# DensityAltitude.net
KiCad netlist of a schematic drawn in EAGLE
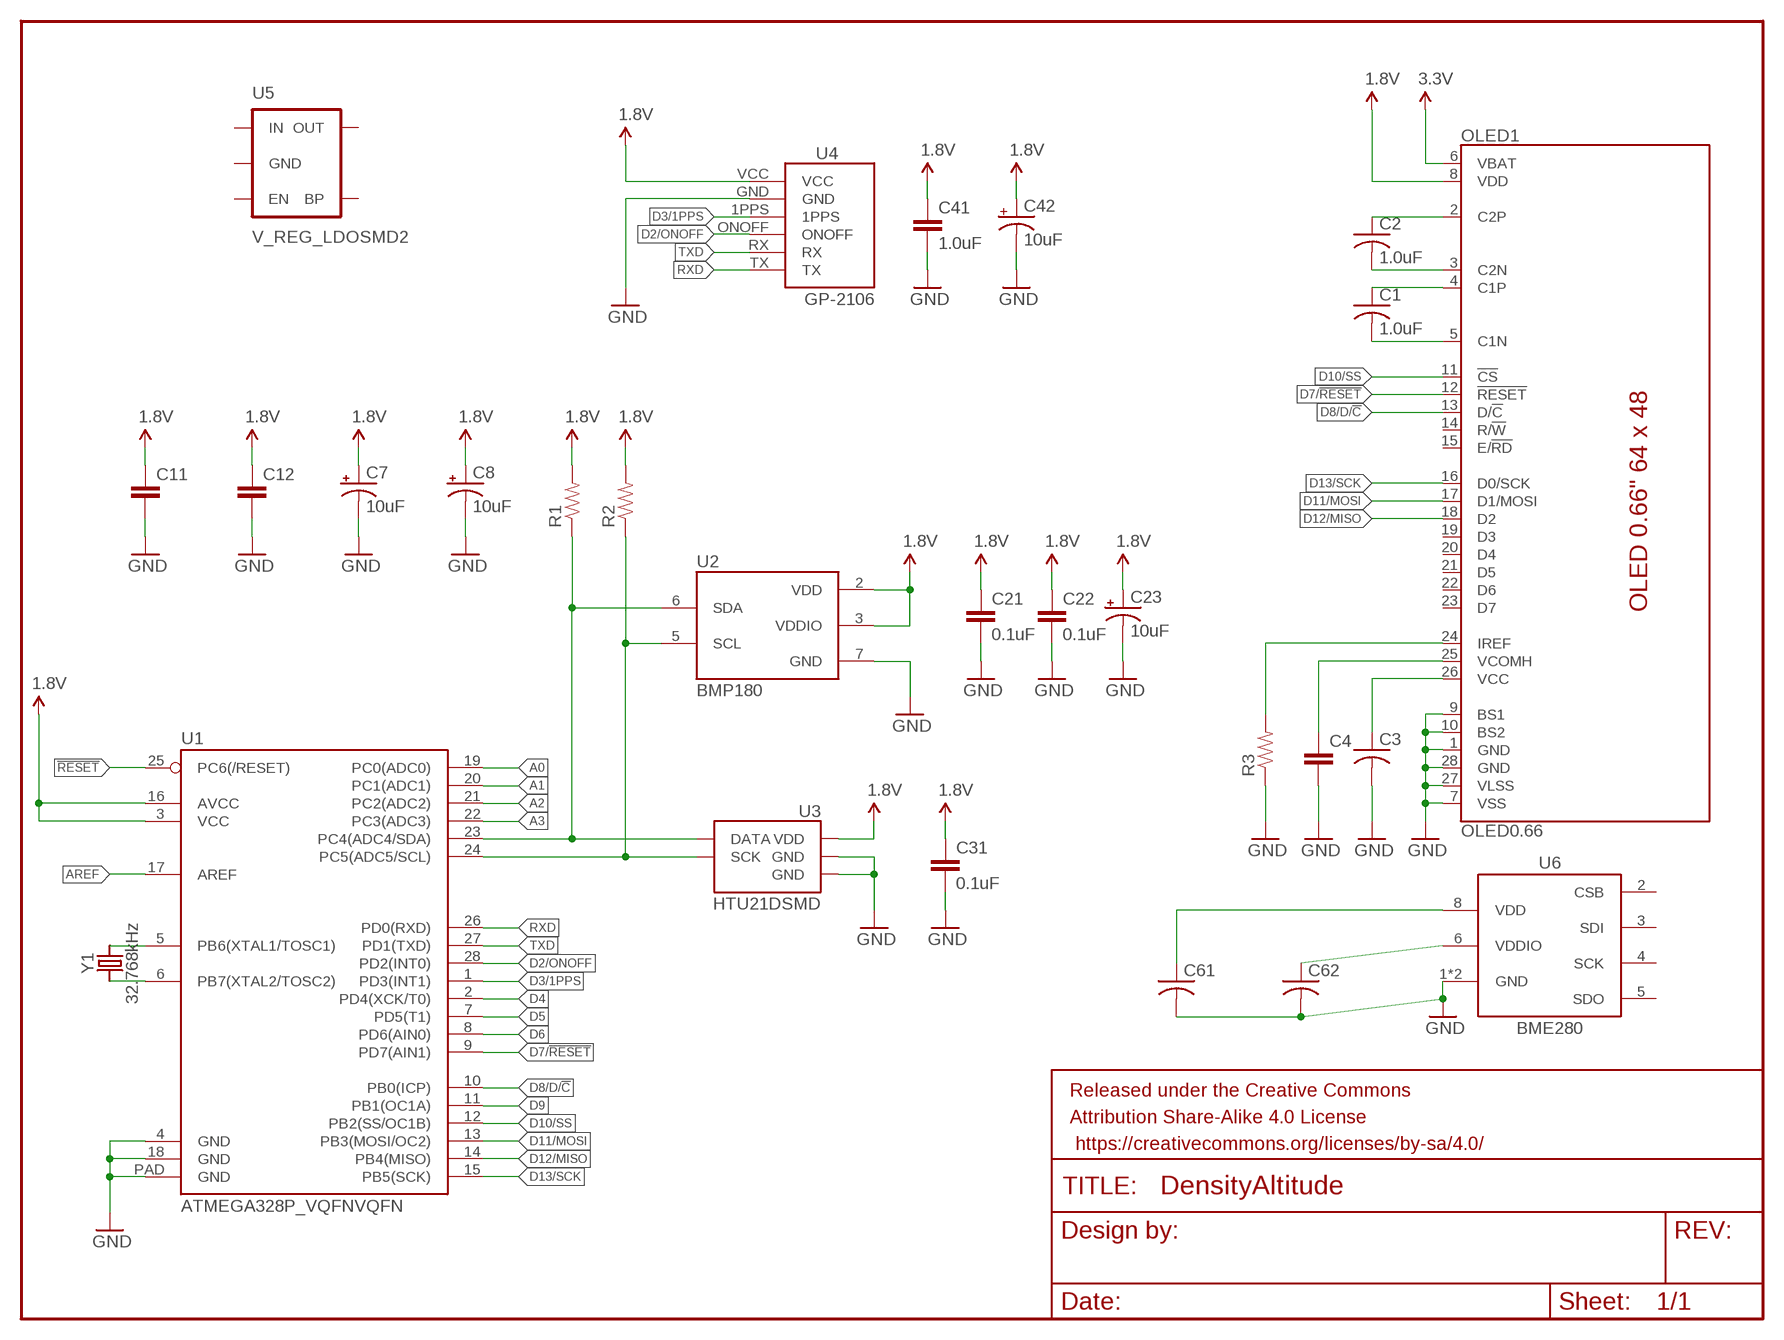
[diagram p0: schematic, sheet 1]

(export (version "E")
  (design (tool "Eeschema 10.0.6"))
  (components
    (comp (ref "C1")
      (value "1.0uF")
      (footprint "eagle-import:C0201")
      (libsource (lib "eagle-import") (part "C-USC0201"))
    )
    (comp (ref "C2")
      (value "1.0uF")
      (footprint "eagle-import:C0201")
      (libsource (lib "eagle-import") (part "C-USC0201"))
    )
    (comp (ref "C3")
      (value "C-USC0201")
      (footprint "eagle-import:C0201")
      (libsource (lib "eagle-import") (part "C-USC0201"))
    )
    (comp (ref "C4")
      (value "CAP0402-CAP")
      (footprint "eagle-import:0402-CAP")
      (libsource (lib "eagle-import") (part "CAP0402-CAP"))
    )
    (comp (ref "C7")
      (value "10uF")
      (footprint "eagle-import:EIA3216")
      (libsource (lib "eagle-import") (part "10UF-16V-10%(TANT)"))
    )
    (comp (ref "C8")
      (value "10uF")
      (footprint "eagle-import:EIA3216")
      (libsource (lib "eagle-import") (part "10UF-16V-10%(TANT)"))
    )
    (comp (ref "C11")
      (value "CAP0402-CAP")
      (footprint "eagle-import:0402-CAP")
      (libsource (lib "eagle-import") (part "CAP0402-CAP"))
    )
    (comp (ref "C12")
      (value "CAP0402-CAP")
      (footprint "eagle-import:0402-CAP")
      (libsource (lib "eagle-import") (part "CAP0402-CAP"))
    )
    (comp (ref "C21")
      (value "0.1uF")
      (footprint "eagle-import:0402-CAP")
      (libsource (lib "eagle-import") (part "0.1UF-16V(+-10%)(0402)"))
    )
    (comp (ref "C22")
      (value "0.1uF")
      (footprint "eagle-import:0402-CAP")
      (libsource (lib "eagle-import") (part "0.1UF-16V(+-10%)(0402)"))
    )
    (comp (ref "C23")
      (value "10uF")
      (footprint "eagle-import:EIA3216")
      (libsource (lib "eagle-import") (part "10UF-16V-10%(TANT)"))
    )
    (comp (ref "C31")
      (value "0.1uF")
      (footprint "eagle-import:0402-CAP")
      (libsource (lib "eagle-import") (part "0.1UF-16V(+-10%)(0402)"))
    )
    (comp (ref "C41")
      (value "1.0uF")
      (footprint "eagle-import:0402-CAP")
      (libsource (lib "eagle-import") (part "1.0UF-16V-10%(0402)"))
    )
    (comp (ref "C42")
      (value "10uF")
      (footprint "eagle-import:EIA3216")
      (libsource (lib "eagle-import") (part "10UF-16V-10%(TANT)"))
    )
    (comp (ref "C61")
      (value "C-USC0201")
      (footprint "eagle-import:C0201")
      (libsource (lib "eagle-import") (part "C-USC0201"))
    )
    (comp (ref "C62")
      (value "C-USC0201")
      (footprint "eagle-import:C0201")
      (libsource (lib "eagle-import") (part "C-USC0201"))
    )
    (comp (ref "FRAME1")
      (value "FRAME-LETTER")
      (footprint "eagle-import:CREATIVE_COMMONS")
      (fields (field (name "DESIGNER") "NAME"))
      (libsource (lib "eagle-import") (part "FRAME-LETTER"))
    )
    (comp (ref "OLED1")
      (value "OLED0.66")
      (footprint "eagle-import:OLED-0.66-64X48")
      (libsource (lib "eagle-import") (part "OLED0.66"))
    )
    (comp (ref "R1")
      (value "RESISTOR0402-RES")
      (footprint "eagle-import:0402-RES")
      (libsource (lib "eagle-import") (part "RESISTOR0402-RES"))
    )
    (comp (ref "R2")
      (value "RESISTOR0402-RES")
      (footprint "eagle-import:0402-RES")
      (libsource (lib "eagle-import") (part "RESISTOR0402-RES"))
    )
    (comp (ref "R3")
      (value "RESISTOR0402-RES")
      (footprint "eagle-import:0402-RES")
      (libsource (lib "eagle-import") (part "RESISTOR0402-RES"))
    )
    (comp (ref "U1")
      (value "ATMEGA328P_VQFNVQFN")
      (footprint "eagle-import:VQFN-28")
      (libsource (lib "eagle-import") (part "ATMEGA328P_VQFNVQFN"))
    )
    (comp (ref "U2")
      (value "BMP180")
      (footprint "eagle-import:BMP180")
      (libsource (lib "eagle-import") (part "BMP180"))
    )
    (comp (ref "U3")
      (value "HTU21DSMD")
      (footprint "eagle-import:HTU21D")
      (libsource (lib "eagle-import") (part "HTU21DSMD"))
    )
    (comp (ref "U4")
      (value "GP-2106")
      (footprint "eagle-import:GP-2106")
      (libsource (lib "eagle-import") (part "GP-2106"))
    )
    (comp (ref "U5")
      (value "V_REG_LDOSMD2")
      (footprint "eagle-import:SC70")
      (libsource (lib "eagle-import") (part "V_REG_LDOSMD2"))
    )
    (comp (ref "U6")
      (value "BME280")
      (footprint "eagle-import:BME280")
      (libsource (lib "eagle-import") (part "BME280"))
    )
    (comp (ref "Y1")
      (value "32.768kHz")
      (footprint "eagle-import:2-SMD")
      (libsource (lib "eagle-import") (part "FX12232.768KHZ"))
    )
  )
  (nets
    (net (code "1") (name "/D7{slash}~{RESET}") (class "Default")
      (node (ref "OLED1") (pin "12") (pinfunction "~{RESET}_12") (pintype "bidirectional"))
      (node (ref "U1") (pin "9") (pinfunction "PD7(AIN1)_9") (pintype "bidirectional"))
    )
    (net (code "2") (name "/D8{slash}D{slash}~{C}") (class "Default")
      (node (ref "OLED1") (pin "13") (pinfunction "D/~{C}_13") (pintype "bidirectional"))
      (node (ref "U1") (pin "10") (pinfunction "PB0(ICP)_10") (pintype "bidirectional"))
    )
    (net (code "3") (name "/~{RESET}") (class "Default")
      (node (ref "U1") (pin "25") (pinfunction "PC6(/RESET)_25") (pintype "bidirectional"))
    )
    (net (code "4") (name "1.8V") (class "Default")
      (node (ref "C11") (pin "1") (pinfunction "1_1") (pintype "passive"))
      (node (ref "C12") (pin "1") (pinfunction "1_1") (pintype "passive"))
      (node (ref "C21") (pin "1") (pinfunction "1_1") (pintype "passive"))
      (node (ref "C22") (pin "1") (pinfunction "1_1") (pintype "passive"))
      (node (ref "C23") (pin "A") (pinfunction "+_A") (pintype "passive"))
      (node (ref "C31") (pin "1") (pinfunction "1_1") (pintype "passive"))
      (node (ref "C41") (pin "1") (pinfunction "1_1") (pintype "passive"))
      (node (ref "C42") (pin "A") (pinfunction "+_A") (pintype "passive"))
      (node (ref "C7") (pin "A") (pinfunction "+_A") (pintype "passive"))
      (node (ref "C8") (pin "A") (pinfunction "+_A") (pintype "passive"))
      (node (ref "OLED1") (pin "8") (pinfunction "VDD_8") (pintype "bidirectional"))
      (node (ref "R1") (pin "2") (pinfunction "2_2") (pintype "passive"))
      (node (ref "R2") (pin "2") (pinfunction "2_2") (pintype "passive"))
      (node (ref "U1") (pin "16") (pinfunction "AVCC_16") (pintype "bidirectional"))
      (node (ref "U1") (pin "3") (pinfunction "VCC_3") (pintype "bidirectional"))
      (node (ref "U2") (pin "2") (pinfunction "VDD_2") (pintype "power_in"))
      (node (ref "U2") (pin "3") (pinfunction "VDDIO_3") (pintype "power_in"))
      (node (ref "U3") (pin "VDD") (pinfunction "VDD_VDD") (pintype "power_in"))
      (node (ref "U4") (pin "VCC") (pinfunction "VCC_VCC") (pintype "bidirectional"))
    )
    (net (code "5") (name "3.3V") (class "Default")
      (node (ref "OLED1") (pin "6") (pinfunction "VBAT_6") (pintype "bidirectional"))
    )
    (net (code "6") (name "A0") (class "Default")
      (node (ref "U1") (pin "19") (pinfunction "PC0(ADC0)_19") (pintype "bidirectional"))
    )
    (net (code "7") (name "A1") (class "Default")
      (node (ref "U1") (pin "20") (pinfunction "PC1(ADC1)_20") (pintype "bidirectional"))
    )
    (net (code "8") (name "A2") (class "Default")
      (node (ref "U1") (pin "21") (pinfunction "PC2(ADC2)_21") (pintype "bidirectional"))
    )
    (net (code "9") (name "A3") (class "Default")
      (node (ref "U1") (pin "22") (pinfunction "PC3(ADC3)_22") (pintype "bidirectional"))
    )
    (net (code "10") (name "AREF") (class "Default")
      (node (ref "U1") (pin "17") (pinfunction "AREF_17") (pintype "bidirectional"))
    )
    (net (code "11") (name "D2{slash}ONOFF") (class "Default")
      (node (ref "U1") (pin "28") (pinfunction "PD2(INT0)_28") (pintype "bidirectional"))
      (node (ref "U4") (pin "ONOFF") (pinfunction "ONOFF_ONOFF") (pintype "bidirectional"))
    )
    (net (code "12") (name "D3{slash}1PPS") (class "Default")
      (node (ref "U1") (pin "1") (pinfunction "PD3(INT1)_1") (pintype "bidirectional"))
      (node (ref "U4") (pin "1PPS") (pinfunction "1PPS_1PPS") (pintype "bidirectional"))
    )
    (net (code "13") (name "D4") (class "Default")
      (node (ref "U1") (pin "2") (pinfunction "PD4(XCK/T0)_2") (pintype "bidirectional"))
    )
    (net (code "14") (name "D5") (class "Default")
      (node (ref "U1") (pin "7") (pinfunction "PD5(T1)_7") (pintype "bidirectional"))
    )
    (net (code "15") (name "D6") (class "Default")
      (node (ref "U1") (pin "8") (pinfunction "PD6(AIN0)_8") (pintype "bidirectional"))
    )
    (net (code "16") (name "D9") (class "Default")
      (node (ref "U1") (pin "11") (pinfunction "PB1(OC1A)_11") (pintype "bidirectional"))
    )
    (net (code "17") (name "D10{slash}SS") (class "Default")
      (node (ref "OLED1") (pin "11") (pinfunction "~{CS}_11") (pintype "bidirectional"))
      (node (ref "U1") (pin "12") (pinfunction "PB2(SS/OC1B)_12") (pintype "bidirectional"))
    )
    (net (code "18") (name "D11{slash}MOSI") (class "Default")
      (node (ref "OLED1") (pin "17") (pinfunction "D1/MOSI_17") (pintype "bidirectional"))
      (node (ref "U1") (pin "13") (pinfunction "PB3(MOSI/OC2)_13") (pintype "bidirectional"))
    )
    (net (code "19") (name "D12{slash}MISO") (class "Default")
      (node (ref "OLED1") (pin "18") (pinfunction "D2_18") (pintype "bidirectional"))
      (node (ref "U1") (pin "14") (pinfunction "PB4(MISO)_14") (pintype "bidirectional"))
    )
    (net (code "20") (name "D13{slash}SCK") (class "Default")
      (node (ref "OLED1") (pin "16") (pinfunction "D0/SCK_16") (pintype "bidirectional"))
      (node (ref "U1") (pin "15") (pinfunction "PB5(SCK)_15") (pintype "bidirectional"))
    )
    (net (code "21") (name "GND") (class "Default")
      (node (ref "C11") (pin "2") (pinfunction "2_2") (pintype "passive"))
      (node (ref "C12") (pin "2") (pinfunction "2_2") (pintype "passive"))
      (node (ref "C21") (pin "2") (pinfunction "2_2") (pintype "passive"))
      (node (ref "C22") (pin "2") (pinfunction "2_2") (pintype "passive"))
      (node (ref "C23") (pin "C") (pinfunction "-_C") (pintype "passive"))
      (node (ref "C3") (pin "2") (pinfunction "2_2") (pintype "passive"))
      (node (ref "C31") (pin "2") (pinfunction "2_2") (pintype "passive"))
      (node (ref "C4") (pin "2") (pinfunction "2_2") (pintype "passive"))
      (node (ref "C41") (pin "2") (pinfunction "2_2") (pintype "passive"))
      (node (ref "C42") (pin "C") (pinfunction "-_C") (pintype "passive"))
      (node (ref "C61") (pin "2") (pinfunction "2_2") (pintype "passive"))
      (node (ref "C62") (pin "2") (pinfunction "2_2") (pintype "passive"))
      (node (ref "C7") (pin "C") (pinfunction "-_C") (pintype "passive"))
      (node (ref "C8") (pin "C") (pinfunction "-_C") (pintype "passive"))
      (node (ref "OLED1") (pin "1") (pinfunction "GND_1") (pintype "bidirectional"))
      (node (ref "OLED1") (pin "10") (pinfunction "BS2_10") (pintype "bidirectional"))
      (node (ref "OLED1") (pin "27") (pinfunction "VLSS_27") (pintype "bidirectional"))
      (node (ref "OLED1") (pin "28") (pinfunction "GND_28") (pintype "bidirectional"))
      (node (ref "OLED1") (pin "7") (pinfunction "VSS_7") (pintype "bidirectional"))
      (node (ref "OLED1") (pin "9") (pinfunction "BS1_9") (pintype "bidirectional"))
      (node (ref "R3") (pin "1") (pinfunction "1_1") (pintype "passive"))
      (node (ref "U1") (pin "18") (pinfunction "GND_18") (pintype "bidirectional"))
      (node (ref "U1") (pin "4") (pinfunction "GND_4") (pintype "bidirectional"))
      (node (ref "U1") (pin "PAD") (pinfunction "GND_PAD") (pintype "bidirectional"))
      (node (ref "U2") (pin "7") (pinfunction "GND_7") (pintype "power_in"))
      (node (ref "U3") (pin "7") (pinfunction "GND_7") (pintype "power_in"))
      (node (ref "U3") (pin "GND") (pinfunction "GND_GND") (pintype "power_in"))
      (node (ref "U4") (pin "GND") (pinfunction "GND_GND") (pintype "bidirectional"))
      (node (ref "U6") (pin "1") (pinfunction "GND_1") (pintype "passive"))
      (node (ref "U6") (pin "7") (pinfunction "GND_7") (pintype "passive"))
    )
    (net (code "22") (name "Net-(OLED1-C1N)") (class "Default")
      (node (ref "C1") (pin "2") (pinfunction "2_2") (pintype "passive"))
      (node (ref "OLED1") (pin "5") (pinfunction "C1N_5") (pintype "bidirectional"))
    )
    (net (code "23") (name "Net-(OLED1-C1P)") (class "Default")
      (node (ref "C1") (pin "1") (pinfunction "1_1") (pintype "passive"))
      (node (ref "OLED1") (pin "4") (pinfunction "C1P_4") (pintype "bidirectional"))
    )
    (net (code "24") (name "Net-(OLED1-C2N)") (class "Default")
      (node (ref "C2") (pin "2") (pinfunction "2_2") (pintype "passive"))
      (node (ref "OLED1") (pin "3") (pinfunction "C2N_3") (pintype "bidirectional"))
    )
    (net (code "25") (name "Net-(OLED1-C2P)") (class "Default")
      (node (ref "C2") (pin "1") (pinfunction "1_1") (pintype "passive"))
      (node (ref "OLED1") (pin "2") (pinfunction "C2P_2") (pintype "bidirectional"))
    )
    (net (code "26") (name "Net-(OLED1-IREF)") (class "Default")
      (node (ref "OLED1") (pin "24") (pinfunction "IREF_24") (pintype "bidirectional"))
      (node (ref "R3") (pin "2") (pinfunction "2_2") (pintype "passive"))
    )
    (net (code "27") (name "Net-(OLED1-VCC)") (class "Default")
      (node (ref "C3") (pin "1") (pinfunction "1_1") (pintype "passive"))
      (node (ref "OLED1") (pin "26") (pinfunction "VCC_26") (pintype "bidirectional"))
    )
    (net (code "28") (name "Net-(OLED1-VCOMH)") (class "Default")
      (node (ref "C4") (pin "1") (pinfunction "1_1") (pintype "passive"))
      (node (ref "OLED1") (pin "25") (pinfunction "VCOMH_25") (pintype "bidirectional"))
    )
    (net (code "29") (name "Net-(U1-PB6(XTAL1{slash}TOSC1))") (class "Default")
      (node (ref "U1") (pin "5") (pinfunction "PB6(XTAL1/TOSC1)_5") (pintype "bidirectional"))
      (node (ref "Y1") (pin "2") (pinfunction "2_2") (pintype "passive"))
    )
    (net (code "30") (name "Net-(U1-PB7(XTAL2{slash}TOSC2))") (class "Default")
      (node (ref "U1") (pin "6") (pinfunction "PB7(XTAL2/TOSC2)_6") (pintype "bidirectional"))
      (node (ref "Y1") (pin "1") (pinfunction "1_1") (pintype "passive"))
    )
    (net (code "31") (name "Net-(U1-PC4(ADC4{slash}SDA))") (class "Default")
      (node (ref "R1") (pin "1") (pinfunction "1_1") (pintype "passive"))
      (node (ref "U1") (pin "23") (pinfunction "PC4(ADC4/SDA)_23") (pintype "bidirectional"))
      (node (ref "U2") (pin "6") (pinfunction "SDA_6") (pintype "bidirectional"))
      (node (ref "U3") (pin "DATA") (pinfunction "DATA_DATA") (pintype "bidirectional"))
    )
    (net (code "32") (name "Net-(U1-PC5(ADC5{slash}SCL))") (class "Default")
      (node (ref "R2") (pin "1") (pinfunction "1_1") (pintype "passive"))
      (node (ref "U1") (pin "24") (pinfunction "PC5(ADC5/SCL)_24") (pintype "bidirectional"))
      (node (ref "U2") (pin "5") (pinfunction "SCL_5") (pintype "input"))
      (node (ref "U3") (pin "SCK") (pinfunction "SCK_SCK") (pintype "input"))
    )
    (net (code "33") (name "Net-(U6-VDD)") (class "Default")
      (node (ref "C61") (pin "1") (pinfunction "1_1") (pintype "passive"))
      (node (ref "U6") (pin "8") (pinfunction "VDD_8") (pintype "power_in"))
    )
    (net (code "34") (name "Net-(U6-VDDIO)") (class "Default")
      (node (ref "C62") (pin "1") (pinfunction "1_1") (pintype "passive"))
      (node (ref "U6") (pin "6") (pinfunction "VDDIO_6") (pintype "power_in"))
    )
    (net (code "35") (name "RXD") (class "Default")
      (node (ref "U1") (pin "26") (pinfunction "PD0(RXD)_26") (pintype "bidirectional"))
      (node (ref "U4") (pin "TX") (pinfunction "TX_TX") (pintype "bidirectional"))
    )
    (net (code "36") (name "TXD") (class "Default")
      (node (ref "U1") (pin "27") (pinfunction "PD1(TXD)_27") (pintype "bidirectional"))
      (node (ref "U4") (pin "RX") (pinfunction "RX_RX") (pintype "bidirectional"))
    )
    (net (code "37") (name "unconnected-(OLED1-D3-Pad19)") (class "Default")
      (node (ref "OLED1") (pin "19") (pinfunction "D3_19") (pintype "bidirectional"))
    )
    (net (code "38") (name "unconnected-(OLED1-D4-Pad20)") (class "Default")
      (node (ref "OLED1") (pin "20") (pinfunction "D4_20") (pintype "bidirectional"))
    )
    (net (code "39") (name "unconnected-(OLED1-D5-Pad21)") (class "Default")
      (node (ref "OLED1") (pin "21") (pinfunction "D5_21") (pintype "bidirectional"))
    )
    (net (code "40") (name "unconnected-(OLED1-D6-Pad22)") (class "Default")
      (node (ref "OLED1") (pin "22") (pinfunction "D6_22") (pintype "bidirectional"))
    )
    (net (code "41") (name "unconnected-(OLED1-D7-Pad23)") (class "Default")
      (node (ref "OLED1") (pin "23") (pinfunction "D7_23") (pintype "bidirectional"))
    )
    (net (code "42") (name "unconnected-(OLED1-E{slash}~{RD}-Pad15)") (class "Default")
      (node (ref "OLED1") (pin "15") (pinfunction "E/~{RD}_15") (pintype "bidirectional"))
    )
    (net (code "43") (name "unconnected-(OLED1-R{slash}~{W}-Pad14)") (class "Default")
      (node (ref "OLED1") (pin "14") (pinfunction "R/~{W}_14") (pintype "bidirectional"))
    )
    (net (code "44") (name "unconnected-(U5-BP-Pad4)") (class "Default")
      (node (ref "U5") (pin "4") (pinfunction "BP_4") (pintype "input"))
    )
    (net (code "45") (name "unconnected-(U5-EN-Pad3)") (class "Default")
      (node (ref "U5") (pin "3") (pinfunction "EN_3") (pintype "input"))
    )
    (net (code "46") (name "unconnected-(U5-GND-Pad2)") (class "Default")
      (node (ref "U5") (pin "2") (pinfunction "GND_2") (pintype "input"))
    )
    (net (code "47") (name "unconnected-(U5-IN-Pad1)") (class "Default")
      (node (ref "U5") (pin "1") (pinfunction "IN_1") (pintype "input"))
    )
    (net (code "48") (name "unconnected-(U5-OUT-Pad5)") (class "Default")
      (node (ref "U5") (pin "5") (pinfunction "OUT_5") (pintype "passive"))
    )
    (net (code "49") (name "unconnected-(U6-CSB-Pad2)") (class "Default")
      (node (ref "U6") (pin "2") (pinfunction "CSB_2") (pintype "input"))
    )
    (net (code "50") (name "unconnected-(U6-SCK-Pad4)") (class "Default")
      (node (ref "U6") (pin "4") (pinfunction "SCK_4") (pintype "input"))
    )
    (net (code "51") (name "unconnected-(U6-SDI-Pad3)") (class "Default")
      (node (ref "U6") (pin "3") (pinfunction "SDI_3") (pintype "bidirectional"))
    )
    (net (code "52") (name "unconnected-(U6-SDO-Pad5)") (class "Default")
      (node (ref "U6") (pin "5") (pinfunction "SDO_5") (pintype "bidirectional"))
    )
  )
)
